# connections.net
KiCad netlist of a schematic drawn in Altium Designer
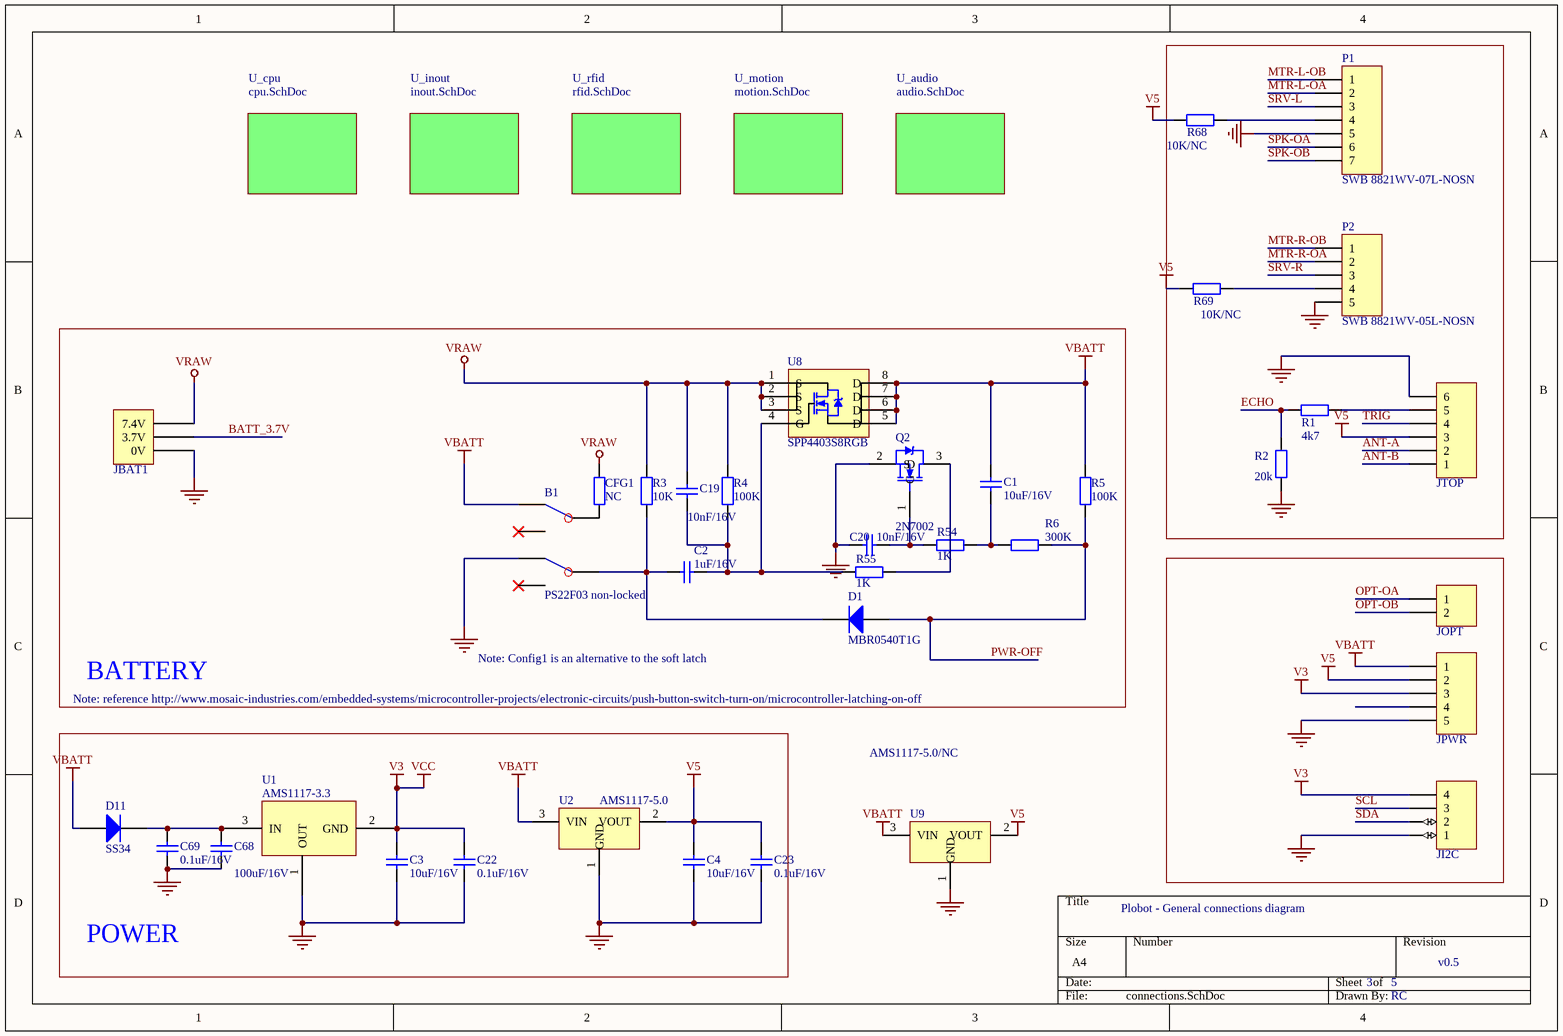
[diagram p0: connections.SchDoc]

(export (version "E")
  (design (tool "Eeschema 10.0.6"))
  (components
    (comp (ref "B1")
      (value "PS22F03 non-locked")
      (footprint "plobot_review:KGPS22F03")
      (libsource (lib "*") (part "Component_1"))
    )
    (comp (ref "C1")
      (value "10uF/16V")
      (footprint "CAPC1608N")
      (description "Capacitor")
      (libsource (lib "main_pcb") (part "Cap_2"))
    )
    (comp (ref "C2")
      (value "1uF/16V")
      (footprint "CAPC1608N")
      (description "Capacitor")
      (libsource (lib "main_pcb") (part "Cap_2"))
    )
    (comp (ref "C3")
      (value "10uF/16V")
      (footprint "CAPC1608N")
      (description "Capacitor")
      (fields (field (name "PUBLISHER") "Altium Limited"))
      (libsource (lib "main_pcb") (part "Cap_2"))
    )
    (comp (ref "C4")
      (value "10uF/16V")
      (footprint "CAPC1608N")
      (description "Capacitor")
      (fields (field (name "PUBLISHER") "Altium Limited"))
      (libsource (lib "main_pcb") (part "Cap_2"))
    )
    (comp (ref "C19")
      (value "10nF/16V")
      (footprint "CAPC1608N")
      (description "Capacitor")
      (libsource (lib "main_pcb") (part "Cap_2"))
    )
    (comp (ref "C20")
      (value "10nF/16V")
      (footprint "CAPC1608N")
      (description "Capacitor")
      (libsource (lib "main_pcb") (part "Cap_2"))
    )
    (comp (ref "C22")
      (value "0.1uF/16V")
      (footprint "CAPC1608N")
      (description "Capacitor")
      (libsource (lib "main_pcb") (part "Cap_2"))
    )
    (comp (ref "C23")
      (value "0.1uF/16V")
      (footprint "CAPC1608N")
      (description "Capacitor")
      (libsource (lib "main_pcb") (part "Cap_2"))
    )
    (comp (ref "C68")
      (value "100uF/16V")
      (footprint "Cap6.6X6.6")
      (description "Capacitor")
      (fields (field (name "PUBLISHER") "Altium Limited"))
      (libsource (lib "Miscellaneous Devices") (part "Cap"))
    )
    (comp (ref "C69")
      (value "0.1uF/16V")
      (footprint "CAPC1608N")
      (description "Capacitor")
      (libsource (lib "main_pcb") (part "Cap_2"))
    )
    (comp (ref "CFG1")
      (value "NC")
      (footprint "plobot_review:RESC1608N")
      (description "Resistor")
      (libsource (lib "*") (part "Res2"))
    )
    (comp (ref "D1")
      (value "MBR0540T1G")
      (footprint "plobot_review:SOD123/X.85")
      (description "Default Diode")
      (libsource (lib "Miscellaneous Devices") (part "Diode"))
    )
    (comp (ref "D11")
      (value "SS34")
      (footprint "SMB")
      (description "1 Amp General Purpose Rectifier")
      (fields (field (name "PUBLISHER") "Altium Limited"))
      (libsource (lib "Miscellaneous Devices") (part "Diode 1N4007"))
    )
    (comp (ref "JBAT1")
      (value "Charger")
      (footprint "plobot_review:S3B-XH-A(LF)(SN)")
      (libsource (lib "components") (part "BATTCON"))
    )
    (comp (ref "JI2C")
      (value "Header 4")
      (footprint "plobot_review:HDR1X4")
      (description "Header, 4-Pin")
      (libsource (lib "Miscellaneous Connectors") (part "Header 4"))
    )
    (comp (ref "JOPT")
      (value "Header 2")
      (footprint "HDR1X2")
      (description "Header, 2-Pin")
      (fields (field (name "PUBLISHER") "Altium Limited"))
      (libsource (lib "Miscellaneous Connectors") (part "Header 2"))
    )
    (comp (ref "JPWR")
      (value "Component")
      (footprint "HDR1X5")
      (description "Header, 5-Pin")
      (fields (field (name "PUBLISHER") "Altium Limited"))
      (libsource (lib "Miscellaneous Connectors") (part "Header 5"))
    )
    (comp (ref "JTOP")
      (value "w/lock")
      (footprint "plobot_review:JST-B6B-XH")
      (description "Header, 6-Pin")
      (libsource (lib "Miscellaneous Connectors") (part "Header 6"))
    )
    (comp (ref "P1")
      (value "SWB 8821WV-07L-NOSN")
      (footprint "XH2.54-7")
      (description "Header, 7-Pin")
      (fields (field (name "PUBLISHER") "Altium Limited"))
      (libsource (lib "Miscellaneous Connectors") (part "Header 7"))
    )
    (comp (ref "P2")
      (value "SWB 8821WV-05L-NOSN")
      (footprint "XH2.54-5")
      (description "Header, 5-Pin")
      (fields (field (name "PUBLISHER") "Altium Limited"))
      (libsource (lib "Miscellaneous Connectors") (part "Header 5"))
    )
    (comp (ref "Q2")
      (value "2N7002")
      (footprint "SOT23")
      (description "NMOS")
      (libsource (lib "SlotmachinePCBlib") (part "2N7002"))
    )
    (comp (ref "R1")
      (value "4k7")
      (footprint "plobot_review:RESC1608N")
      (description "Resistor")
      (fields (field (name "PUBLISHER") "Altium Limited"))
      (libsource (lib "") (part "Res2_4"))
    )
    (comp (ref "R2")
      (value "20k")
      (footprint "RESC1608N")
      (description "Resistor")
      (fields (field (name "PUBLISHER") "Altium Limited"))
      (libsource (lib "*") (part "Res2"))
    )
    (comp (ref "R3")
      (value "10K")
      (footprint "plobot_review:RESC1608N")
      (description "Resistor")
      (libsource (lib "") (part "Res2_1"))
    )
    (comp (ref "R4")
      (value "100K")
      (footprint "plobot_review:RESC1608N")
      (description "Resistor")
      (libsource (lib "") (part "Res2_1"))
    )
    (comp (ref "R5")
      (value "100K")
      (footprint "plobot_review:RESC1608N")
      (description "Resistor")
      (libsource (lib "") (part "Res2_1"))
    )
    (comp (ref "R6")
      (value "300K")
      (footprint "plobot_review:RESC1608N")
      (description "Resistor")
      (libsource (lib "") (part "Res2_3"))
    )
    (comp (ref "R54")
      (value "1K")
      (footprint "RESC1608N")
      (description "Resistor")
      (libsource (lib "") (part "Res2_2"))
    )
    (comp (ref "R55")
      (value "1K")
      (footprint "RESC1608N")
      (description "Resistor")
      (libsource (lib "") (part "Res2_2"))
    )
    (comp (ref "R68")
      (value "10K/NC")
      (footprint "RESC1608N")
      (description "Resistor")
      (fields (field (name "PUBLISHER") "Altium Limited"))
      (libsource (lib "") (part "Res2_4"))
    )
    (comp (ref "R69")
      (value "10K/NC")
      (footprint "RESC1608N")
      (description "Resistor")
      (fields (field (name "PUBLISHER") "Altium Limited"))
      (libsource (lib "") (part "Res2_4"))
    )
    (comp (ref "U1")
      (value "AMS1117-3.3")
      (footprint "plobot_review:SOT223")
      (libsource (lib "*") (part "LM1117"))
    )
    (comp (ref "U2")
      (value "AMS1117-5.0")
      (footprint "TO252")
      (libsource (lib "COMMODEVICES") (part "LM1117-3.3V"))
    )
    (comp (ref "U8")
      (value "SPP4403S8RGB")
      (footprint "SOP8")
      (libsource (lib "COMMODEVICES") (part "SPP4403S8RGB"))
    )
    (comp (ref "U9")
      (value "AMS1117-5.0/NC")
      (footprint "SOT-223")
      (libsource (lib "COMMODEVICES") (part "LM1117-3.3V"))
    )
  )
  (nets
    (net (code "1") (name "/ANT-A") (class "Default")
      (node (ref "JTOP") (pin "2") (pinfunction "2_2") (pintype "passive"))
    )
    (net (code "2") (name "/ANT-B") (class "Default")
      (node (ref "JTOP") (pin "1") (pinfunction "1_1") (pintype "passive"))
    )
    (net (code "3") (name "/BATT_3.7V") (class "Default")
      (node (ref "JBAT1") (pin "2") (pinfunction "3.7V_2") (pintype "passive"))
    )
    (net (code "4") (name "/ECHO") (class "Default")
      (node (ref "R1") (pin "1") (pinfunction "1_1") (pintype "passive"))
      (node (ref "R2") (pin "1") (pinfunction "1_1") (pintype "passive"))
    )
    (net (code "5") (name "/MTR-L-OA") (class "Default")
      (node (ref "P1") (pin "2") (pinfunction "2_2") (pintype "passive"))
    )
    (net (code "6") (name "/MTR-L-OB") (class "Default")
      (node (ref "P1") (pin "1") (pinfunction "1_1") (pintype "passive"))
    )
    (net (code "7") (name "/MTR-R-OA") (class "Default")
      (node (ref "P2") (pin "2") (pinfunction "2_2") (pintype "passive"))
    )
    (net (code "8") (name "/MTR-R-OB") (class "Default")
      (node (ref "P2") (pin "1") (pinfunction "1_1") (pintype "passive"))
    )
    (net (code "9") (name "/OPT-OA") (class "Default")
      (node (ref "JOPT") (pin "1") (pinfunction "1_1") (pintype "passive"))
    )
    (net (code "10") (name "/OPT-OB") (class "Default")
      (node (ref "JOPT") (pin "2") (pinfunction "2_2") (pintype "passive"))
    )
    (net (code "11") (name "/PWR-OFF") (class "Default")
      (node (ref "D1") (pin "2") (pinfunction "A_2") (pintype "passive"))
      (node (ref "R5") (pin "1") (pinfunction "1_1") (pintype "passive"))
      (node (ref "R6") (pin "1") (pinfunction "1_1") (pintype "passive"))
    )
    (net (code "12") (name "/SCL") (class "Default")
      (node (ref "JI2C") (pin "3") (pinfunction "3_3") (pintype "power_in"))
    )
    (net (code "13") (name "/SDA") (class "Default")
      (node (ref "JI2C") (pin "2") (pinfunction "2_2") (pintype "bidirectional"))
    )
    (net (code "14") (name "/SPK-OA") (class "Default")
      (node (ref "P1") (pin "6") (pinfunction "6_6") (pintype "passive"))
    )
    (net (code "15") (name "/SPK-OB") (class "Default")
      (node (ref "P1") (pin "7") (pinfunction "7_7") (pintype "passive"))
    )
    (net (code "16") (name "/SRV-L") (class "Default")
      (node (ref "P1") (pin "3") (pinfunction "3_3") (pintype "passive"))
    )
    (net (code "17") (name "/SRV-R") (class "Default")
      (node (ref "P2") (pin "3") (pinfunction "3_3") (pintype "passive"))
    )
    (net (code "18") (name "/TRIG") (class "Default")
      (node (ref "JTOP") (pin "4") (pinfunction "4_4") (pintype "passive"))
    )
    (net (code "19") (name "GND") (class "Default")
      (node (ref "B1") (pin "4") (pintype "passive"))
      (node (ref "C20") (pin "1") (pinfunction "1_1") (pintype "passive"))
      (node (ref "C22") (pin "1") (pinfunction "1_1") (pintype "passive"))
      (node (ref "C23") (pin "1") (pinfunction "1_1") (pintype "passive"))
      (node (ref "C3") (pin "2") (pinfunction "2_2") (pintype "passive"))
      (node (ref "C4") (pin "1") (pinfunction "1_1") (pintype "passive"))
      (node (ref "C68") (pin "1") (pinfunction "1_1") (pintype "passive"))
      (node (ref "C69") (pin "1") (pinfunction "1_1") (pintype "passive"))
      (node (ref "JBAT1") (pin "1") (pinfunction "0V_1") (pintype "passive"))
      (node (ref "JI2C") (pin "1") (pinfunction "1_1") (pintype "bidirectional"))
      (node (ref "JPWR") (pin "5") (pinfunction "5_5") (pintype "passive"))
      (node (ref "JTOP") (pin "6") (pinfunction "6_6") (pintype "passive"))
      (node (ref "P1") (pin "5") (pinfunction "5_5") (pintype "passive"))
      (node (ref "P2") (pin "5") (pinfunction "5_5") (pintype "passive"))
      (node (ref "Q2") (pin "2") (pinfunction "S_2") (pintype "passive"))
      (node (ref "R2") (pin "2") (pinfunction "2_2") (pintype "passive"))
      (node (ref "U1") (pin "1") (pinfunction "OUT_1") (pintype "passive"))
      (node (ref "U2") (pin "1") (pinfunction "GND_1") (pintype "power_in"))
      (node (ref "U9") (pin "1") (pinfunction "GND_1") (pintype "power_in"))
    )
    (net (code "20") (name "Net-(B1-Pad2)") (class "Default")
      (node (ref "B1") (pin "2") (pintype "passive"))
      (node (ref "CFG1") (pin "2") (pinfunction "2_2") (pintype "passive"))
    )
    (net (code "21") (name "Net-(C1-Pad2)") (class "Default")
      (node (ref "C1") (pin "2") (pinfunction "2_2") (pintype "passive"))
      (node (ref "R54") (pin "1") (pinfunction "1_1") (pintype "passive"))
      (node (ref "R6") (pin "2") (pinfunction "2_2") (pintype "passive"))
    )
    (net (code "22") (name "Net-(D1-K)") (class "Default")
      (node (ref "B1") (pin "5") (pintype "passive"))
      (node (ref "C2") (pin "1") (pinfunction "1_1") (pintype "passive"))
      (node (ref "D1") (pin "1") (pinfunction "K_1") (pintype "passive"))
      (node (ref "R3") (pin "1") (pinfunction "1_1") (pintype "passive"))
    )
    (net (code "23") (name "Net-(D11-K)") (class "Default")
      (node (ref "C68") (pin "2") (pinfunction "2_2") (pintype "passive"))
      (node (ref "C69") (pin "2") (pinfunction "2_2") (pintype "passive"))
      (node (ref "D11") (pin "2") (pinfunction "K_2") (pintype "passive"))
      (node (ref "U1") (pin "3") (pinfunction "IN_3") (pintype "passive"))
    )
    (net (code "24") (name "Net-(JTOP-Pad5)") (class "Default")
      (node (ref "JTOP") (pin "5") (pinfunction "5_5") (pintype "passive"))
      (node (ref "R1") (pin "2") (pinfunction "2_2") (pintype "passive"))
    )
    (net (code "25") (name "Net-(P1-Pad4)") (class "Default")
      (node (ref "P1") (pin "4") (pinfunction "4_4") (pintype "passive"))
      (node (ref "R68") (pin "2") (pinfunction "2_2") (pintype "passive"))
    )
    (net (code "26") (name "Net-(P2-Pad4)") (class "Default")
      (node (ref "P2") (pin "4") (pinfunction "4_4") (pintype "passive"))
      (node (ref "R69") (pin "2") (pinfunction "2_2") (pintype "passive"))
    )
    (net (code "27") (name "Net-(Q2-D)") (class "Default")
      (node (ref "Q2") (pin "3") (pinfunction "D_3") (pintype "passive"))
      (node (ref "R55") (pin "1") (pinfunction "1_1") (pintype "passive"))
    )
    (net (code "28") (name "Net-(Q2-G)") (class "Default")
      (node (ref "C20") (pin "2") (pinfunction "2_2") (pintype "passive"))
      (node (ref "Q2") (pin "1") (pinfunction "G_1") (pintype "passive"))
      (node (ref "R54") (pin "2") (pinfunction "2_2") (pintype "passive"))
    )
    (net (code "29") (name "Net-(U8-G)") (class "Default")
      (node (ref "C19") (pin "1") (pinfunction "1_1") (pintype "passive"))
      (node (ref "C2") (pin "2") (pinfunction "2_2") (pintype "passive"))
      (node (ref "R4") (pin "1") (pinfunction "1_1") (pintype "passive"))
      (node (ref "R55") (pin "2") (pinfunction "2_2") (pintype "passive"))
      (node (ref "U8") (pin "4") (pinfunction "G_4") (pintype "passive"))
    )
    (net (code "30") (name "V3") (class "Default")
      (node (ref "C22") (pin "2") (pinfunction "2_2") (pintype "passive"))
      (node (ref "C3") (pin "1") (pinfunction "1_1") (pintype "passive"))
      (node (ref "JI2C") (pin "4") (pinfunction "4_4") (pintype "power_in"))
      (node (ref "JPWR") (pin "3") (pinfunction "3_3") (pintype "passive"))
      (node (ref "U1") (pin "2") (pinfunction "GND_2") (pintype "passive"))
    )
    (net (code "31") (name "V5") (class "Default")
      (node (ref "C23") (pin "2") (pinfunction "2_2") (pintype "passive"))
      (node (ref "C4") (pin "2") (pinfunction "2_2") (pintype "passive"))
      (node (ref "JPWR") (pin "2") (pinfunction "2_2") (pintype "passive"))
      (node (ref "JTOP") (pin "3") (pinfunction "3_3") (pintype "passive"))
      (node (ref "R68") (pin "1") (pinfunction "1_1") (pintype "passive"))
      (node (ref "R69") (pin "1") (pinfunction "1_1") (pintype "passive"))
      (node (ref "U2") (pin "2") (pinfunction "VOUT_2") (pintype "power_in"))
      (node (ref "U9") (pin "2") (pinfunction "VOUT_2") (pintype "power_in"))
    )
    (net (code "32") (name "VBATT") (class "Default")
      (node (ref "B1") (pin "3") (pintype "passive"))
      (node (ref "C1") (pin "1") (pinfunction "1_1") (pintype "passive"))
      (node (ref "D11") (pin "1") (pinfunction "A_1") (pintype "passive"))
      (node (ref "JPWR") (pin "1") (pinfunction "1_1") (pintype "passive"))
      (node (ref "R5") (pin "2") (pinfunction "2_2") (pintype "passive"))
      (node (ref "U2") (pin "3") (pinfunction "VIN_3") (pintype "power_in"))
      (node (ref "U8") (pin "5") (pinfunction "D_5") (pintype "passive"))
      (node (ref "U8") (pin "6") (pinfunction "D_6") (pintype "passive"))
      (node (ref "U8") (pin "7") (pinfunction "D_7") (pintype "passive"))
      (node (ref "U8") (pin "8") (pinfunction "D_8") (pintype "passive"))
      (node (ref "U9") (pin "3") (pinfunction "VIN_3") (pintype "power_in"))
    )
    (net (code "33") (name "VRAW") (class "Default")
      (node (ref "C19") (pin "2") (pinfunction "2_2") (pintype "passive"))
      (node (ref "CFG1") (pin "1") (pinfunction "1_1") (pintype "passive"))
      (node (ref "JBAT1") (pin "3") (pinfunction "7.4V_3") (pintype "passive"))
      (node (ref "R3") (pin "2") (pinfunction "2_2") (pintype "passive"))
      (node (ref "R4") (pin "2") (pinfunction "2_2") (pintype "passive"))
      (node (ref "U8") (pin "1") (pinfunction "S_1") (pintype "passive"))
      (node (ref "U8") (pin "2") (pinfunction "S_2") (pintype "passive"))
      (node (ref "U8") (pin "3") (pinfunction "S_3") (pintype "passive"))
    )
    (net (code "34") (name "unconnected-(B1-Pad1)") (class "Default")
      (node (ref "B1") (pin "1") (pintype "passive+no_connect"))
    )
    (net (code "35") (name "unconnected-(B1-Pad6)") (class "Default")
      (node (ref "B1") (pin "6") (pintype "passive+no_connect"))
    )
    (net (code "36") (name "unconnected-(JPWR-Pad4)") (class "Default")
      (node (ref "JPWR") (pin "4") (pinfunction "4_4") (pintype "passive"))
    )
  )
)
